# ultrasonic_rx.net
KiCad netlist of a schematic drawn in Altium Designer
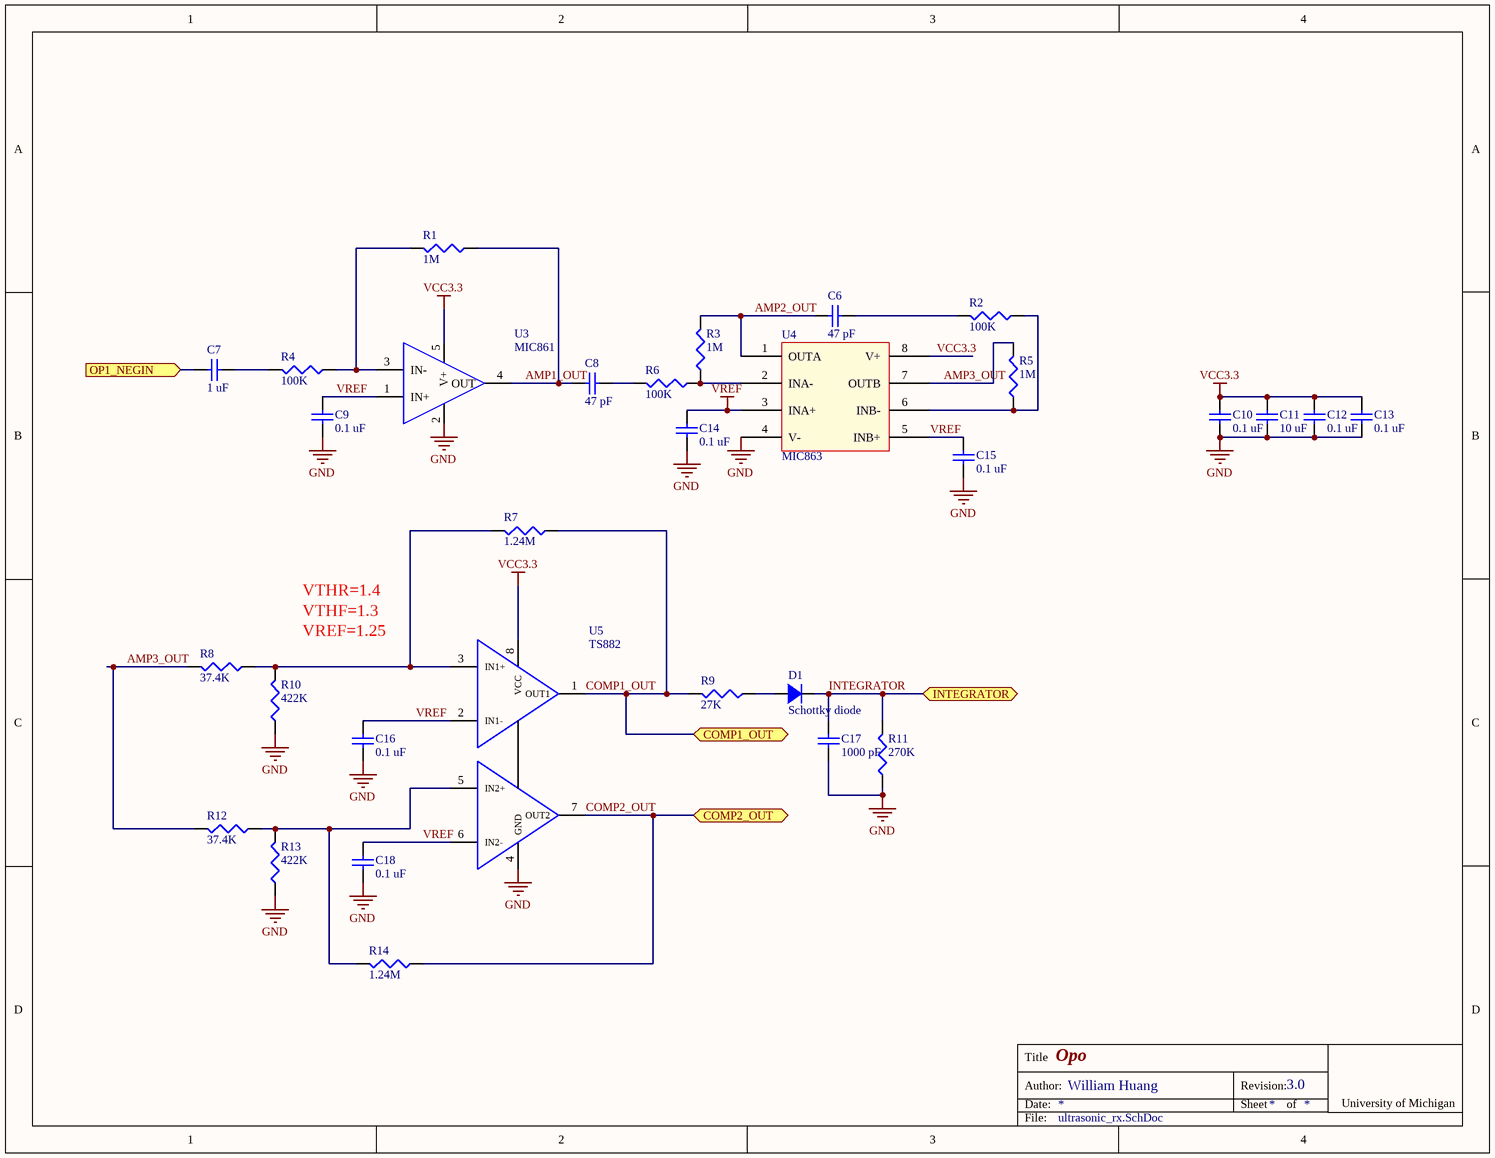
[diagram p0: ultrasonic_rx.SchDoc]

(export (version "E")
  (design (tool "Eeschema 10.0.6"))
  (components
    (comp (ref "C6")
      (value "47 pF")
      (footprint "0402")
      (description "Ceramic capacitor, 47 pF, 0402 package")
      (fields (field (name "TOLERANCE") "5%") (field (name "Comment") "Ceramic capacitor"))
      (libsource (lib "rlc") (part "C_47p_0402_ceramic"))
    )
    (comp (ref "C7")
      (value "1 uF")
      (footprint "0402")
      (description "Ceramic capacitor, 1 uF, 0402 package")
      (fields (field (name "TOLERANCE") "10%") (field (name "Comment") "Ceramic capacitor"))
      (libsource (lib "rlc") (part "C_1u_0402_ceramic"))
    )
    (comp (ref "C8")
      (value "47 pF")
      (footprint "0402")
      (description "Ceramic capacitor, 47 pF, 0402 package")
      (fields (field (name "TOLERANCE") "5%") (field (name "Comment") "Ceramic capacitor"))
      (libsource (lib "rlc") (part "C_47p_0402_ceramic"))
    )
    (comp (ref "C9")
      (value "0.1 uF")
      (footprint "0402")
      (description "Ceramic capacitor, 0.1u, 0402 package")
      (fields (field (name "TOLERANCE") "10%") (field (name "Comment") "Ceramic capacitor"))
      (libsource (lib "rlc") (part "C_0.1u_0402_ceramic"))
    )
    (comp (ref "C10")
      (value "0.1 uF")
      (footprint "0402")
      (description "Ceramic capacitor, 0.1u, 0402 package")
      (fields (field (name "TOLERANCE") "10%") (field (name "Comment") "Ceramic capacitor"))
      (libsource (lib "rlc") (part "C_0.1u_0402_ceramic"))
    )
    (comp (ref "C11")
      (value "10 uF")
      (footprint "0603")
      (description "Ceramic capacitor, 10 uF, 0603 package")
      (fields (field (name "TOLERANCE") "20%") (field (name "Comment") "Ceramic capacitor"))
      (libsource (lib "rlc") (part "C_10u_0603_ceramic"))
    )
    (comp (ref "C12")
      (value "0.1 uF")
      (footprint "0402")
      (description "Ceramic capacitor, 0.1u, 0402 package")
      (fields (field (name "TOLERANCE") "10%") (field (name "Comment") "Ceramic capacitor"))
      (libsource (lib "rlc") (part "C_0.1u_0402_ceramic"))
    )
    (comp (ref "C13")
      (value "0.1 uF")
      (footprint "0402")
      (description "Ceramic capacitor, 0.1u, 0402 package")
      (fields (field (name "TOLERANCE") "10%") (field (name "Comment") "Ceramic capacitor"))
      (libsource (lib "rlc") (part "C_0.1u_0402_ceramic"))
    )
    (comp (ref "C14")
      (value "0.1 uF")
      (footprint "0402")
      (description "Ceramic capacitor, 0.1u, 0402 package")
      (fields (field (name "TOLERANCE") "10%") (field (name "Comment") "Ceramic capacitor"))
      (libsource (lib "rlc") (part "C_0.1u_0402_ceramic"))
    )
    (comp (ref "C15")
      (value "0.1 uF")
      (footprint "0402")
      (description "Ceramic capacitor, 0.1u, 0402 package")
      (fields (field (name "TOLERANCE") "10%") (field (name "Comment") "Ceramic capacitor"))
      (libsource (lib "rlc") (part "C_0.1u_0402_ceramic"))
    )
    (comp (ref "C16")
      (value "0.1 uF")
      (footprint "0402")
      (description "Ceramic capacitor, 0.1u, 0402 package")
      (fields (field (name "TOLERANCE") "10%") (field (name "Comment") "Ceramic capacitor"))
      (libsource (lib "rlc") (part "C_0.1u_0402_ceramic"))
    )
    (comp (ref "C17")
      (value "1000 pF")
      (footprint "0402")
      (description "Ceramic capacitor, 1000 pF, 0402 package")
      (fields (field (name "TOLERANCE") "10%") (field (name "Comment") "Ceramic capacitor"))
      (libsource (lib "rlc") (part "C_1000p_0402_ceramic"))
    )
    (comp (ref "C18")
      (value "0.1 uF")
      (footprint "0402")
      (description "Ceramic capacitor, 0.1u, 0402 package")
      (fields (field (name "TOLERANCE") "10%") (field (name "Comment") "Ceramic capacitor"))
      (libsource (lib "rlc") (part "C_0.1u_0402_ceramic"))
    )
    (comp (ref "D1")
      (value "Schottky diode")
      (footprint "0603 - DIODE")
      (description "Schottky diode 30 V 0.1 A 0603")
      (libsource (lib "rlc") (part "D_SCHOTTKY_30V_0.1A_0603"))
    )
    (comp (ref "R1")
      (value "1M")
      (footprint "0402")
      (description "Chip resistor, 1M, 0402 package")
      (fields (field (name "TOLERANCE") "1%") (field (name "POWER") "1/16 W"))
      (libsource (lib "rlc") (part "R_1M_0402"))
    )
    (comp (ref "R2")
      (value "100K")
      (footprint "0402")
      (description "Chip resistor, 100K, 0402 package")
      (fields (field (name "TOLERANCE") "1%") (field (name "POWER") "1/16 W"))
      (libsource (lib "rlc") (part "R_100K_0402"))
    )
    (comp (ref "R3")
      (value "1M")
      (footprint "0402")
      (description "Chip resistor, 1M, 0402 package")
      (fields (field (name "TOLERANCE") "1%") (field (name "POWER") "1/16 W"))
      (libsource (lib "rlc") (part "R_1M_0402"))
    )
    (comp (ref "R4")
      (value "100K")
      (footprint "0402")
      (description "Chip resistor, 100K, 0402 package")
      (fields (field (name "TOLERANCE") "1%") (field (name "POWER") "1/16 W"))
      (libsource (lib "rlc") (part "R_100K_0402"))
    )
    (comp (ref "R5")
      (value "1M")
      (footprint "0402")
      (description "Chip resistor, 1M, 0402 package")
      (fields (field (name "TOLERANCE") "1%") (field (name "POWER") "1/16 W"))
      (libsource (lib "rlc") (part "R_1M_0402"))
    )
    (comp (ref "R6")
      (value "100K")
      (footprint "0402")
      (description "Chip resistor, 100K, 0402 package")
      (fields (field (name "TOLERANCE") "1%") (field (name "POWER") "1/16 W"))
      (libsource (lib "rlc") (part "R_100K_0402"))
    )
    (comp (ref "R7")
      (value "1.24M")
      (footprint "0402")
      (description "Chip resistor, 1.24M, 0402 package")
      (fields (field (name "TOLERANCE") "1%") (field (name "POWER") "1/16 W"))
      (libsource (lib "rlc") (part "R_1.24M_0402"))
    )
    (comp (ref "R8")
      (value "37.4K")
      (footprint "0402")
      (description "Chip resistor, 37.4K, 0402 package")
      (fields (field (name "TOLERANCE") "1%") (field (name "POWER") "1/16 W"))
      (libsource (lib "rlc") (part "R_37.4K_0402"))
    )
    (comp (ref "R9")
      (value "27K")
      (footprint "0402")
      (description "Chip resistor, 27K, 0402 package")
      (fields (field (name "TOLERANCE") "1%") (field (name "POWER") "1/16 W"))
      (libsource (lib "rlc") (part "R_27K_0402"))
    )
    (comp (ref "R10")
      (value "422K")
      (footprint "0402")
      (description "Chip resistor, 422K, 0402 package")
      (fields (field (name "TOLERANCE") "1%") (field (name "POWER") "1/16 W"))
      (libsource (lib "rlc") (part "R_422K_0402"))
    )
    (comp (ref "R11")
      (value "270K")
      (footprint "0402")
      (description "Chip resistor, 270K, 0402 package")
      (fields (field (name "TOLERANCE") "1%") (field (name "POWER") "1/16 W"))
      (libsource (lib "rlc") (part "R_270K_0402"))
    )
    (comp (ref "R12")
      (value "37.4K")
      (footprint "0402")
      (description "Chip resistor, 37.4K, 0402 package")
      (fields (field (name "TOLERANCE") "1%") (field (name "POWER") "1/16 W"))
      (libsource (lib "rlc") (part "R_37.4K_0402"))
    )
    (comp (ref "R13")
      (value "422K")
      (footprint "0402")
      (description "Chip resistor, 422K, 0402 package")
      (fields (field (name "TOLERANCE") "1%") (field (name "POWER") "1/16 W"))
      (libsource (lib "rlc") (part "R_422K_0402"))
    )
    (comp (ref "R14")
      (value "1.24M")
      (footprint "0402")
      (description "Chip resistor, 1.24M, 0402 package")
      (fields (field (name "TOLERANCE") "1%") (field (name "POWER") "1/16 W"))
      (libsource (lib "rlc") (part "R_1.24M_0402"))
    )
    (comp (ref "U3")
      (value "MIC861")
      (footprint "SC70-5")
      (description "IC OPAMP 400KHZ 2.7V ULT LP SC70")
      (libsource (lib "opo_general") (part "MIC861"))
    )
    (comp (ref "U4")
      (value "MIC863")
      (footprint "TSOP65P280X145-8N")
      (description "Dual Ultra Low Power Op Amp in SOT23-8")
      (libsource (lib "opo_general") (part "MIC863"))
    )
    (comp (ref "U5")
      (value "TS882")
      (footprint "SO8")
      (description "Ultra Low Power Dual Comparator")
      (libsource (lib "opo_general") (part "TS882"))
    )
  )
  (nets
    (net (code "1") (name "/AMP1_OUT") (class "Default")
      (node (ref "C8") (pin "1") (pintype "passive"))
      (node (ref "R1") (pin "2") (pintype "passive"))
      (node (ref "U3") (pin "4") (pinfunction "OUT_4") (pintype "passive"))
    )
    (net (code "2") (name "/AMP2_OUT") (class "Default")
      (node (ref "C6") (pin "1") (pintype "passive"))
      (node (ref "R3") (pin "1") (pintype "passive"))
      (node (ref "U4") (pin "1") (pinfunction "OUTA_1") (pintype "passive"))
    )
    (net (code "3") (name "/AMP3_OUT") (class "Default")
      (node (ref "R12") (pin "1") (pintype "passive"))
      (node (ref "R5") (pin "1") (pintype "passive"))
      (node (ref "R8") (pin "1") (pintype "passive"))
      (node (ref "U4") (pin "7") (pinfunction "OUTB_7") (pintype "passive"))
    )
    (net (code "4") (name "/COMP1_OUT") (class "Default")
      (node (ref "R7") (pin "2") (pintype "passive"))
      (node (ref "R9") (pin "1") (pintype "passive"))
      (node (ref "U5") (pin "1") (pinfunction "OUT1_1") (pintype "passive"))
    )
    (net (code "5") (name "/COMP2_OUT") (class "Default")
      (node (ref "R14") (pin "2") (pintype "passive"))
      (node (ref "U5") (pin "7") (pinfunction "OUT2_7") (pintype "passive"))
    )
    (net (code "6") (name "/INTEGRATOR") (class "Default")
      (node (ref "C17") (pin "1") (pintype "passive"))
      (node (ref "D1") (pin "2") (pintype "passive"))
      (node (ref "R11") (pin "1") (pintype "passive"))
    )
    (net (code "7") (name "/OP1_NEGIN") (class "Default") (node (ref "C7") (pin "1") (pintype "passive")))
    (net (code "8") (name "GND") (class "Default")
      (node (ref "C10") (pin "2") (pintype "passive"))
      (node (ref "C11") (pin "2") (pintype "passive"))
      (node (ref "C12") (pin "2") (pintype "passive"))
      (node (ref "C13") (pin "2") (pintype "passive"))
      (node (ref "C14") (pin "2") (pintype "passive"))
      (node (ref "C15") (pin "2") (pintype "passive"))
      (node (ref "C16") (pin "2") (pintype "passive"))
      (node (ref "C17") (pin "2") (pintype "passive"))
      (node (ref "C18") (pin "2") (pintype "passive"))
      (node (ref "C9") (pin "2") (pintype "passive"))
      (node (ref "R10") (pin "2") (pintype "passive"))
      (node (ref "R11") (pin "2") (pintype "passive"))
      (node (ref "R13") (pin "2") (pintype "passive"))
      (node (ref "U3") (pin "2") (pinfunction "V-_2") (pintype "passive"))
      (node (ref "U4") (pin "4") (pinfunction "V-_4") (pintype "passive"))
      (node (ref "U5") (pin "4") (pinfunction "GND_4") (pintype "passive"))
    )
    (net (code "9") (name "Net-(C6-Pad2)") (class "Default")
      (node (ref "C6") (pin "2") (pintype "passive"))
      (node (ref "R2") (pin "1") (pintype "passive"))
    )
    (net (code "10") (name "Net-(C7-Pad2)") (class "Default")
      (node (ref "C7") (pin "2") (pintype "passive"))
      (node (ref "R4") (pin "1") (pintype "passive"))
    )
    (net (code "11") (name "Net-(C8-Pad2)") (class "Default")
      (node (ref "C8") (pin "2") (pintype "passive"))
      (node (ref "R6") (pin "1") (pintype "passive"))
    )
    (net (code "12") (name "Net-(D1-Pad1)") (class "Default")
      (node (ref "D1") (pin "1") (pintype "passive"))
      (node (ref "R9") (pin "2") (pintype "passive"))
    )
    (net (code "13") (name "Net-(U3-IN-)") (class "Default")
      (node (ref "R1") (pin "1") (pintype "passive"))
      (node (ref "R4") (pin "2") (pintype "passive"))
      (node (ref "U3") (pin "3") (pinfunction "IN-_3") (pintype "passive"))
    )
    (net (code "14") (name "Net-(U4-INA-)") (class "Default")
      (node (ref "R3") (pin "2") (pintype "passive"))
      (node (ref "R6") (pin "2") (pintype "passive"))
      (node (ref "U4") (pin "2") (pinfunction "INA-_2") (pintype "passive"))
    )
    (net (code "15") (name "Net-(U4-INB-)") (class "Default")
      (node (ref "R2") (pin "2") (pintype "passive"))
      (node (ref "R5") (pin "2") (pintype "passive"))
      (node (ref "U4") (pin "6") (pinfunction "INB-_6") (pintype "passive"))
    )
    (net (code "16") (name "Net-(U5-IN1+)") (class "Default")
      (node (ref "R10") (pin "1") (pintype "passive"))
      (node (ref "R7") (pin "1") (pintype "passive"))
      (node (ref "R8") (pin "2") (pintype "passive"))
      (node (ref "U5") (pin "3") (pinfunction "IN1+_3") (pintype "passive"))
    )
    (net (code "17") (name "Net-(U5-IN2+)") (class "Default")
      (node (ref "R12") (pin "2") (pintype "passive"))
      (node (ref "R13") (pin "1") (pintype "passive"))
      (node (ref "R14") (pin "1") (pintype "passive"))
      (node (ref "U5") (pin "5") (pinfunction "IN2+_5") (pintype "passive"))
    )
    (net (code "18") (name "VCC3.3") (class "Default")
      (node (ref "C10") (pin "1") (pintype "passive"))
      (node (ref "C11") (pin "1") (pintype "passive"))
      (node (ref "C12") (pin "1") (pintype "passive"))
      (node (ref "C13") (pin "1") (pintype "passive"))
      (node (ref "U3") (pin "5") (pinfunction "V+_5") (pintype "passive"))
      (node (ref "U4") (pin "8") (pinfunction "V+_8") (pintype "passive"))
      (node (ref "U5") (pin "8") (pinfunction "VCC_8") (pintype "passive"))
    )
    (net (code "19") (name "VREF") (class "Default")
      (node (ref "C14") (pin "1") (pintype "passive"))
      (node (ref "C15") (pin "1") (pintype "passive"))
      (node (ref "C16") (pin "1") (pintype "passive"))
      (node (ref "C18") (pin "1") (pintype "passive"))
      (node (ref "C9") (pin "1") (pintype "passive"))
      (node (ref "U3") (pin "1") (pinfunction "IN+_1") (pintype "passive"))
      (node (ref "U4") (pin "3") (pinfunction "INA+_3") (pintype "passive"))
      (node (ref "U4") (pin "5") (pinfunction "INB+_5") (pintype "passive"))
      (node (ref "U5") (pin "2") (pinfunction "IN1-_2") (pintype "passive"))
      (node (ref "U5") (pin "6") (pinfunction "IN2-_6") (pintype "passive"))
    )
  )
)
